# design.net
KiCad netlist of a schematic drawn in EAGLE
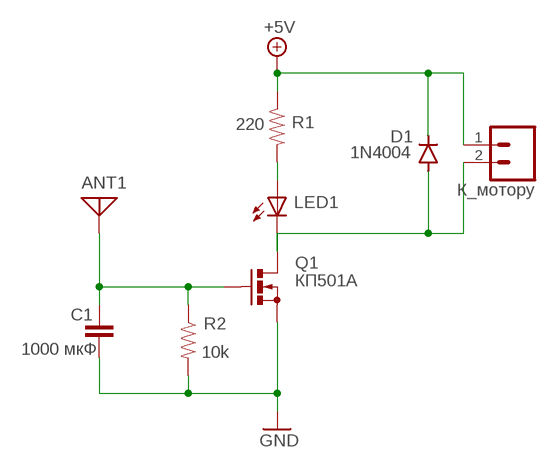
[diagram p0: schematic, sheet 1]

(export (version "E")
  (design (tool "Eeschema 10.0.6"))
  (components
    (comp (ref "ANT1")
      (value "ANTENNA")
      (footprint "eagle-import:PAD-01")
      (libsource (lib "eagle-import") (part "ANTENNA"))
    )
    (comp (ref "C1")
      (value "1000 мкФ")
      (footprint "eagle-import:C5B3")
      (libsource (lib "eagle-import") (part "C5/3"))
    )
    (comp (ref "D1")
      (value "1N4004")
      (footprint "eagle-import:DO41-10")
      (libsource (lib "eagle-import") (part "1N4004"))
    )
    (comp (ref "LED1")
      (value "LED5MM")
      (footprint "eagle-import:LED5MM")
      (libsource (lib "eagle-import") (part "LED5MM"))
    )
    (comp (ref "Q1")
      (value "КП501А")
      (footprint "eagle-import:SOT54E")
      (libsource (lib "eagle-import") (part "BS170"))
    )
    (comp (ref "R1")
      (value "220")
      (footprint "eagle-import:AXIAL-0.3")
      (libsource (lib "eagle-import") (part "100OHM-HORIZ-1/4W-1%"))
    )
    (comp (ref "R2")
      (value "10k")
      (footprint "eagle-import:AXIAL-0.3")
      (libsource (lib "eagle-import") (part "100OHM-HORIZ-1/4W-1%"))
    )
    (comp (ref "К_мотору")
      (value "CONN_02")
      (footprint "eagle-import:1X02")
      (libsource (lib "eagle-import") (part "CONN_02"))
    )
  )
  (nets
    (net (code "1") (name "+5V") (class "Default")
      (node (ref "D1") (pin "C") (pinfunction "C_C") (pintype "passive"))
      (node (ref "R1") (pin "P$1") (pinfunction "1_P$1") (pintype "passive"))
      (node (ref "К_мотору") (pin "1") (pinfunction "1_1") (pintype "passive"))
    )
    (net (code "2") (name "GND") (class "Default")
      (node (ref "C1") (pin "2") (pinfunction "2_2") (pintype "passive"))
      (node (ref "Q1") (pin "S") (pinfunction "S_S") (pintype "passive"))
      (node (ref "R2") (pin "P$2") (pinfunction "2_P$2") (pintype "passive"))
    )
    (net (code "3") (name "Net-(LED1-C)") (class "Default")
      (node (ref "D1") (pin "A") (pinfunction "A_A") (pintype "passive"))
      (node (ref "LED1") (pin "K") (pinfunction "C_K") (pintype "passive"))
      (node (ref "Q1") (pin "D") (pinfunction "D_D") (pintype "passive"))
      (node (ref "К_мотору") (pin "2") (pinfunction "2_2") (pintype "passive"))
    )
    (net (code "4") (name "Net-(R1-2)") (class "Default")
      (node (ref "LED1") (pin "A") (pinfunction "A_A") (pintype "passive"))
      (node (ref "R1") (pin "P$2") (pinfunction "2_P$2") (pintype "passive"))
    )
    (net (code "5") (name "Net-(R2-1)") (class "Default")
      (node (ref "ANT1") (pin "1") (pinfunction "1_1") (pintype "output"))
      (node (ref "C1") (pin "1") (pinfunction "1_1") (pintype "passive"))
      (node (ref "Q1") (pin "G") (pinfunction "G_G") (pintype "passive"))
      (node (ref "R2") (pin "P$1") (pinfunction "1_P$1") (pintype "passive"))
    )
  )
)
